# PATTERN-GENERATOR-NODE-SCH.net
KiCad netlist of a schematic drawn in Altium Designer
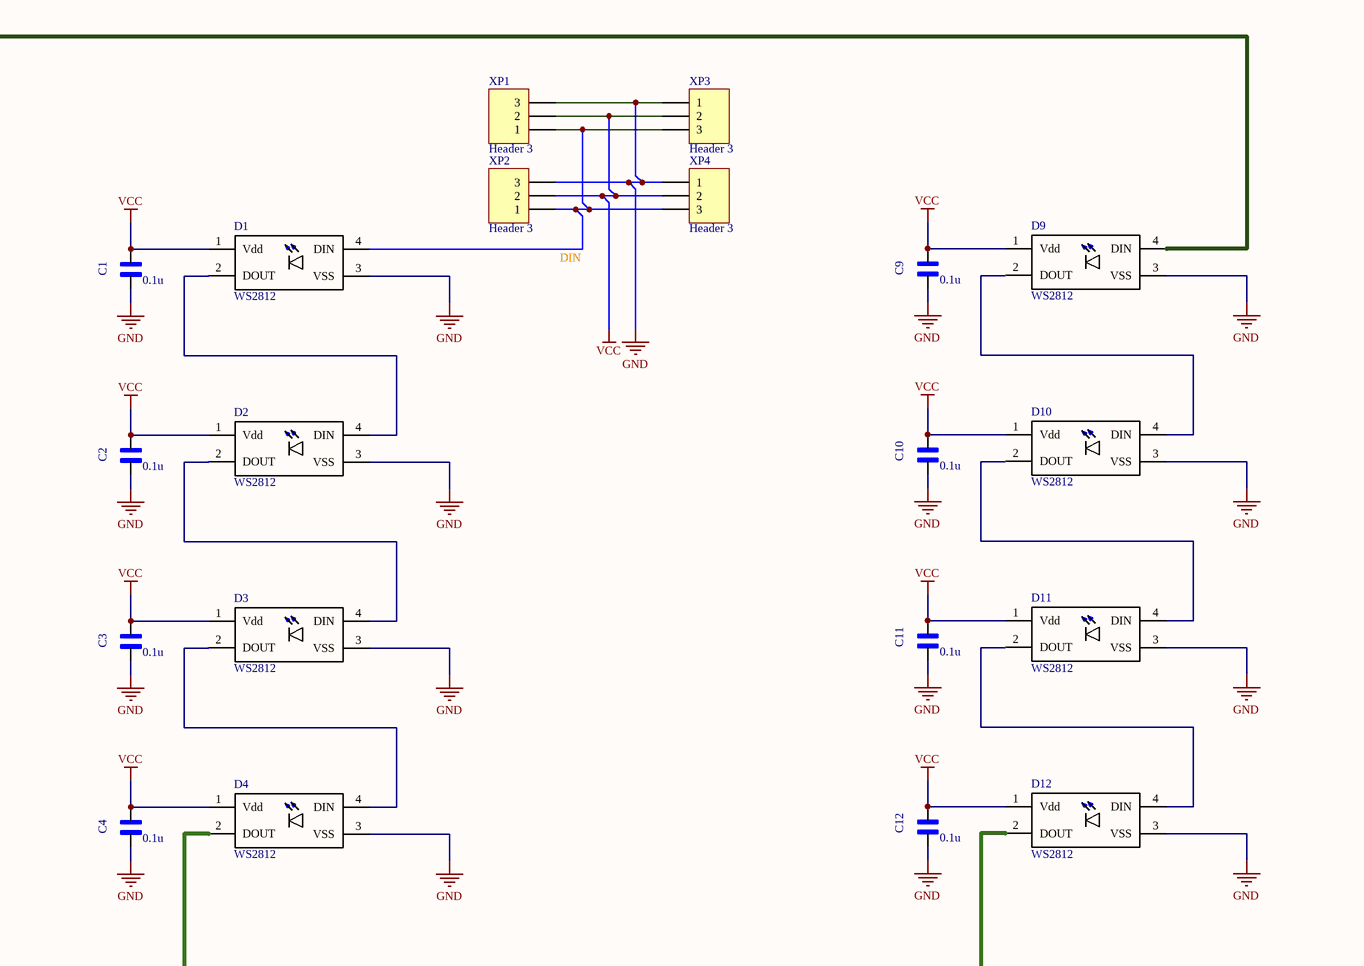
[diagram p0: PATTERN-GENERATOR-NODE-SCH.SchDoc, top left]
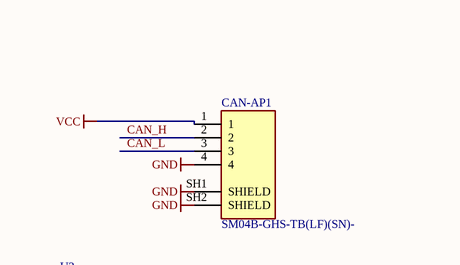
[diagram p1: PATTERN-GENERATOR-NODE-SCH.SchDoc, top right]
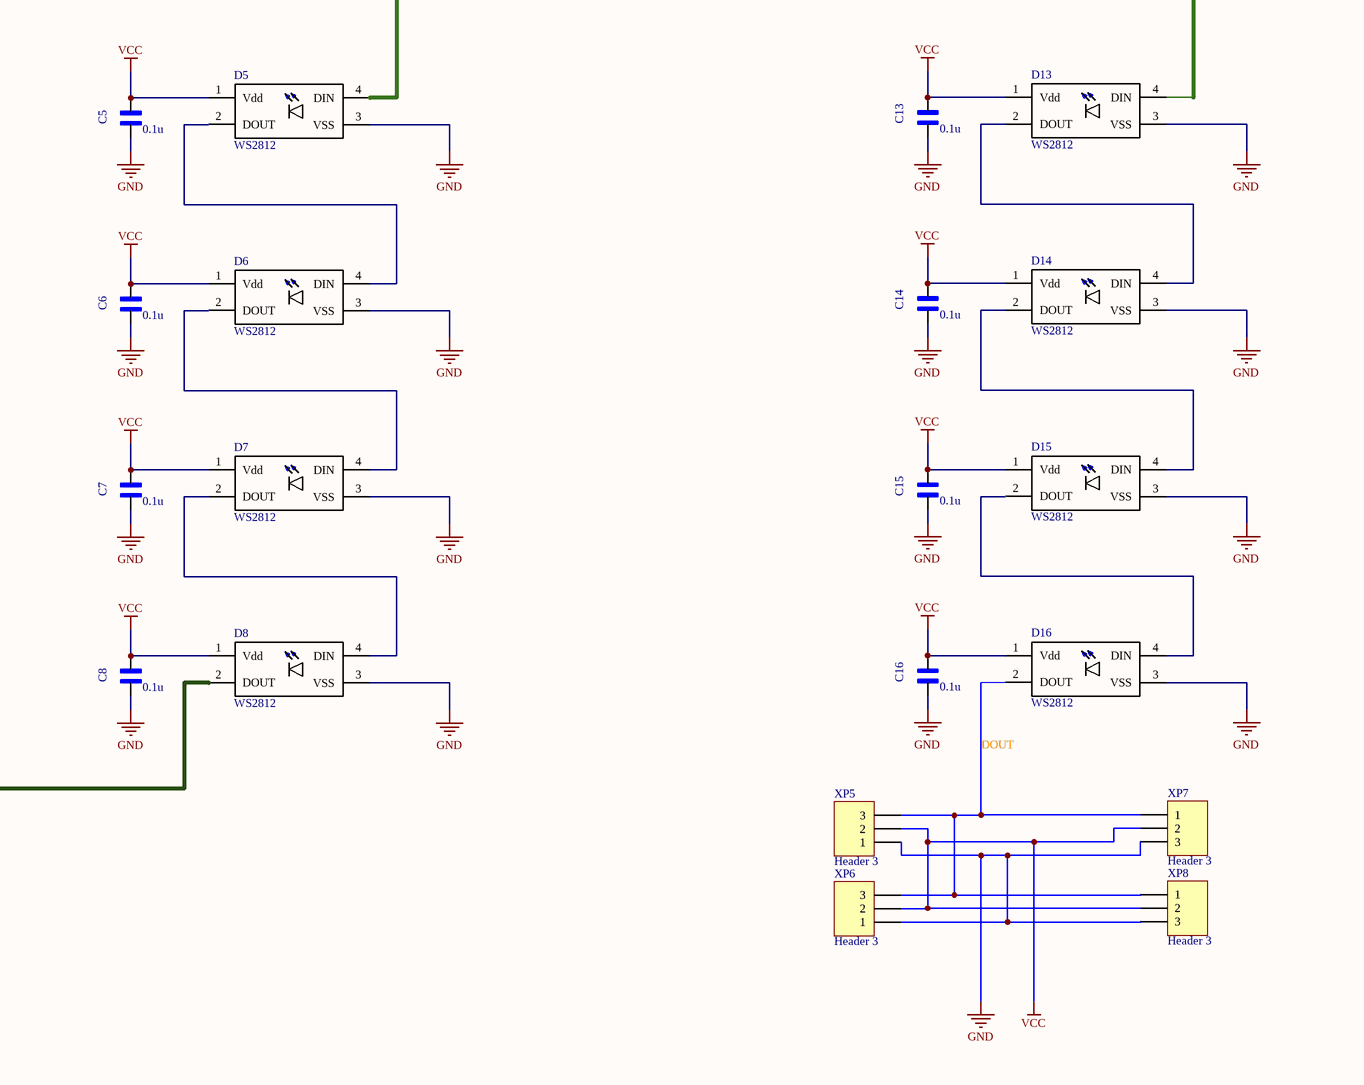
[diagram p2: PATTERN-GENERATOR-NODE-SCH.SchDoc, bottom left]
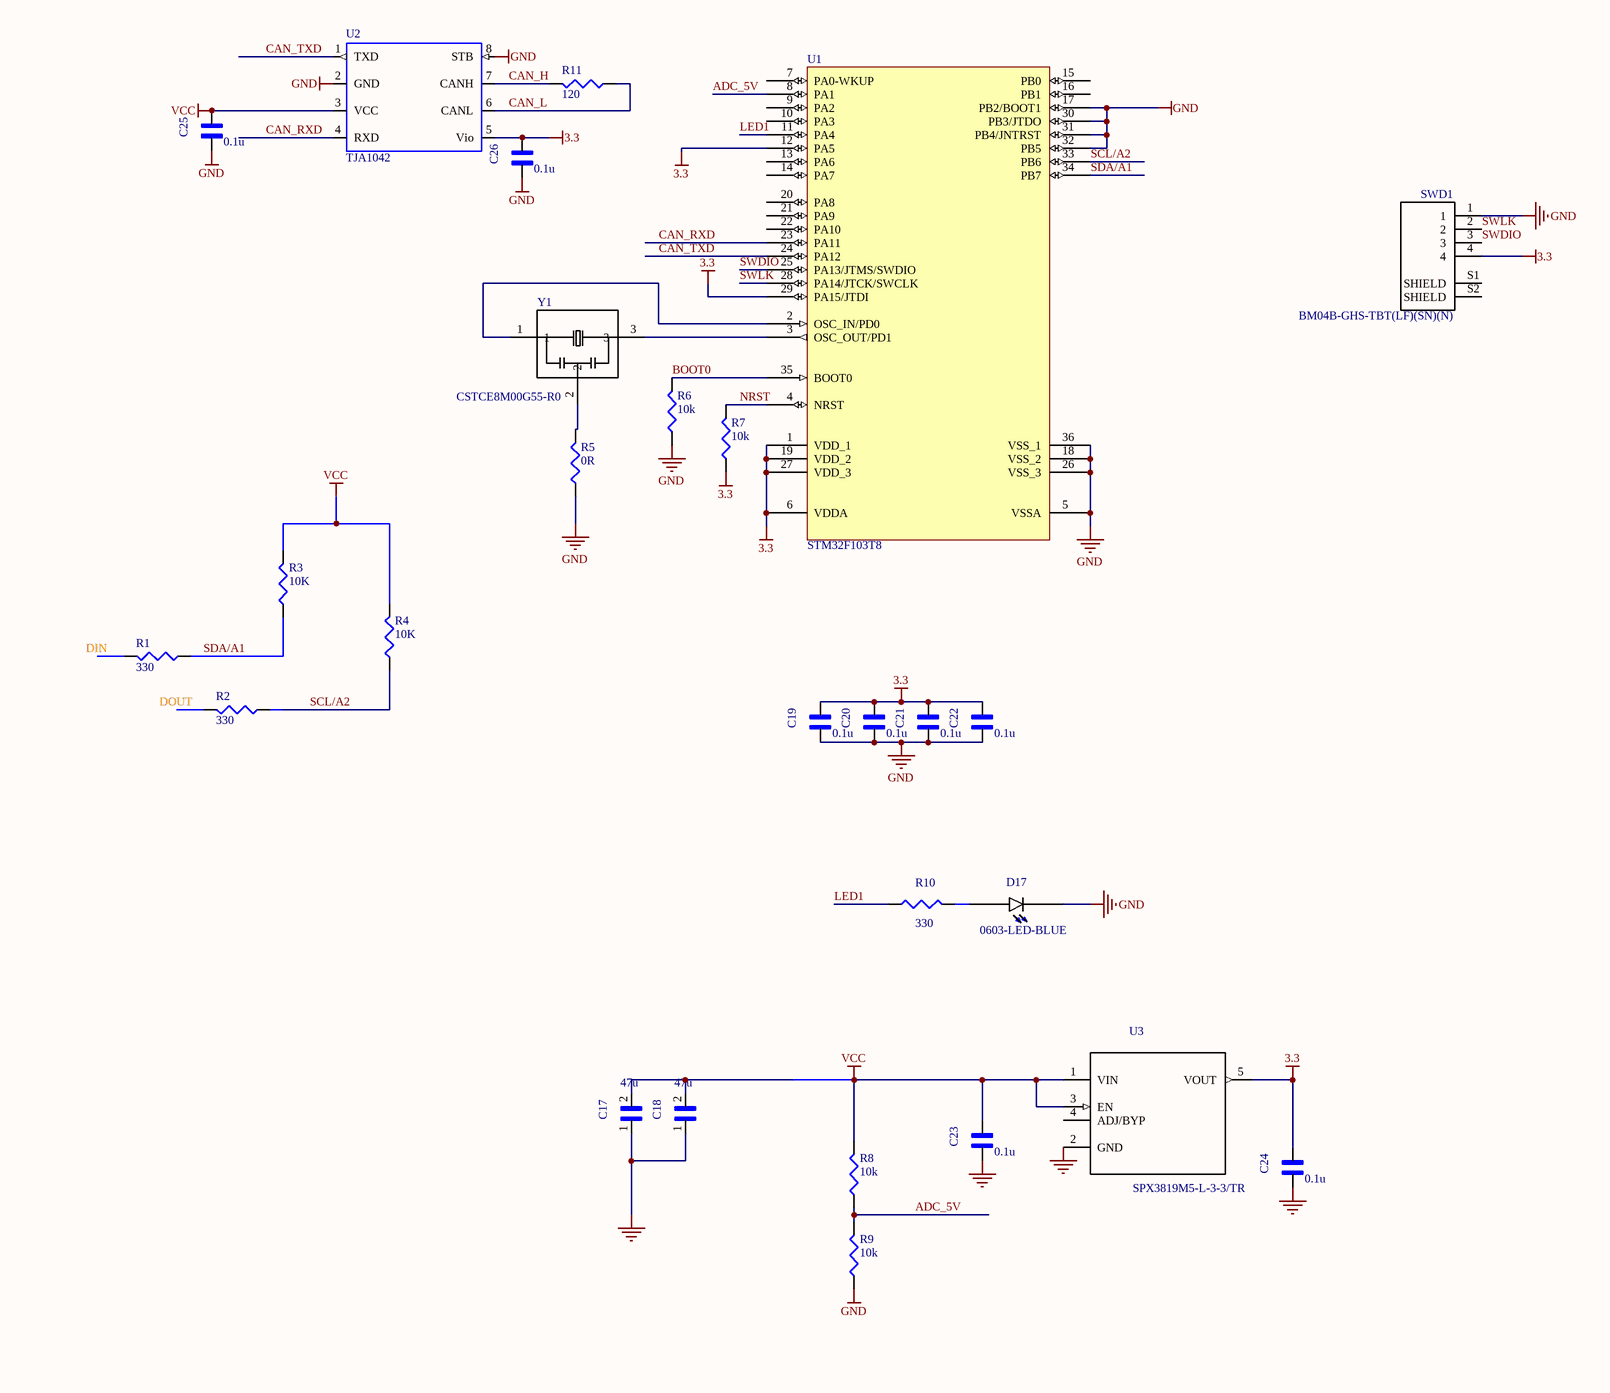
[diagram p3: PATTERN-GENERATOR-NODE-SCH.SchDoc, bottom right]

(export (version "E")
  (design (tool "Eeschema 10.0.6"))
  (components
    (comp (ref "C1")
      (value "0.1u")
      (footprint "*CAPC1608X90")
      (description "Cap Thin Film 0.1uf 50v 0603")
      (fields (field (name "MF") "AVX") (field (name "MP") "GX035C104MAT2-500 or CL10B104JB8NNNC"))
      (libsource (lib "lib") (part "GX035C104MAT2-500"))
    )
    (comp (ref "C2")
      (value "0.1u")
      (footprint "*CAPC1608X90")
      (description "Cap Thin Film 0.1uf 50v 0603")
      (fields (field (name "MF") "AVX") (field (name "MP") "GX035C104MAT2-500 or CL10B104JB8NNNC"))
      (libsource (lib "lib") (part "GX035C104MAT2-500"))
    )
    (comp (ref "C3")
      (value "0.1u")
      (footprint "*CAPC1608X90")
      (description "Cap Thin Film 0.1uf 50v 0603")
      (fields (field (name "MF") "AVX") (field (name "MP") "GX035C104MAT2-500 or CL10B104JB8NNNC"))
      (libsource (lib "lib") (part "GX035C104MAT2-500"))
    )
    (comp (ref "C4")
      (value "0.1u")
      (footprint "*CAPC1608X90")
      (description "Cap Thin Film 0.1uf 50v 0603")
      (fields (field (name "MF") "AVX") (field (name "MP") "GX035C104MAT2-500 or CL10B104JB8NNNC"))
      (libsource (lib "lib") (part "GX035C104MAT2-500"))
    )
    (comp (ref "C5")
      (value "0.1u")
      (footprint "*CAPC1608X90")
      (description "Cap Thin Film 0.1uf 50v 0603")
      (fields (field (name "MF") "AVX") (field (name "MP") "GX035C104MAT2-500 or CL10B104JB8NNNC"))
      (libsource (lib "lib") (part "GX035C104MAT2-500"))
    )
    (comp (ref "C6")
      (value "0.1u")
      (footprint "*CAPC1608X90")
      (description "Cap Thin Film 0.1uf 50v 0603")
      (fields (field (name "MF") "AVX") (field (name "MP") "GX035C104MAT2-500 or CL10B104JB8NNNC"))
      (libsource (lib "lib") (part "GX035C104MAT2-500"))
    )
    (comp (ref "C7")
      (value "0.1u")
      (footprint "*CAPC1608X90")
      (description "Cap Thin Film 0.1uf 50v 0603")
      (fields (field (name "MF") "AVX") (field (name "MP") "GX035C104MAT2-500 or CL10B104JB8NNNC"))
      (libsource (lib "lib") (part "GX035C104MAT2-500"))
    )
    (comp (ref "C8")
      (value "0.1u")
      (footprint "*CAPC1608X90")
      (description "Cap Thin Film 0.1uf 50v 0603")
      (fields (field (name "MF") "AVX") (field (name "MP") "GX035C104MAT2-500 or CL10B104JB8NNNC"))
      (libsource (lib "lib") (part "GX035C104MAT2-500"))
    )
    (comp (ref "C9")
      (value "0.1u")
      (footprint "*CAPC1608X90")
      (description "Cap Thin Film 0.1uf 50v 0603")
      (fields (field (name "MF") "AVX") (field (name "MP") "GX035C104MAT2-500 or CL10B104JB8NNNC"))
      (libsource (lib "lib") (part "GX035C104MAT2-500"))
    )
    (comp (ref "C10")
      (value "0.1u")
      (footprint "*CAPC1608X90")
      (description "Cap Thin Film 0.1uf 50v 0603")
      (fields (field (name "MF") "AVX") (field (name "MP") "GX035C104MAT2-500 or CL10B104JB8NNNC"))
      (libsource (lib "lib") (part "GX035C104MAT2-500"))
    )
    (comp (ref "C11")
      (value "0.1u")
      (footprint "*CAPC1608X90")
      (description "Cap Thin Film 0.1uf 50v 0603")
      (fields (field (name "MF") "AVX") (field (name "MP") "GX035C104MAT2-500 or CL10B104JB8NNNC"))
      (libsource (lib "lib") (part "GX035C104MAT2-500"))
    )
    (comp (ref "C12")
      (value "0.1u")
      (footprint "*CAPC1608X90")
      (description "Cap Thin Film 0.1uf 50v 0603")
      (fields (field (name "MF") "AVX") (field (name "MP") "GX035C104MAT2-500 or CL10B104JB8NNNC"))
      (libsource (lib "lib") (part "GX035C104MAT2-500"))
    )
    (comp (ref "C13")
      (value "0.1u")
      (footprint "*CAPC1608X90")
      (description "Cap Thin Film 0.1uf 50v 0603")
      (fields (field (name "MF") "AVX") (field (name "MP") "GX035C104MAT2-500 or CL10B104JB8NNNC"))
      (libsource (lib "lib") (part "GX035C104MAT2-500"))
    )
    (comp (ref "C14")
      (value "0.1u")
      (footprint "*CAPC1608X90")
      (description "Cap Thin Film 0.1uf 50v 0603")
      (fields (field (name "MF") "AVX") (field (name "MP") "GX035C104MAT2-500 or CL10B104JB8NNNC"))
      (libsource (lib "lib") (part "GX035C104MAT2-500"))
    )
    (comp (ref "C15")
      (value "0.1u")
      (footprint "*CAPC1608X90")
      (description "Cap Thin Film 0.1uf 50v 0603")
      (fields (field (name "MF") "AVX") (field (name "MP") "GX035C104MAT2-500 or CL10B104JB8NNNC"))
      (libsource (lib "lib") (part "GX035C104MAT2-500"))
    )
    (comp (ref "C16")
      (value "0.1u")
      (footprint "*CAPC1608X90")
      (description "Cap Thin Film 0.1uf 50v 0603")
      (fields (field (name "MF") "AVX") (field (name "MP") "GX035C104MAT2-500 or CL10B104JB8NNNC"))
      (libsource (lib "lib") (part "GX035C104MAT2-500"))
    )
    (comp (ref "C17")
      (value "47u")
      (footprint "*CAPC3216X125N")
      (description "Multilayer Ceramic Capacitor, GRM Series, 47 - F, - 10%, X5R, 10 V, 1206 [3216 Metric]")
      (fields (field (name "MF") "Murata Electronics") (field (name "MP") "GRM31CR61A476KE15L"))
      (libsource (lib "lib") (part "GRM31CR61A476KE15L"))
    )
    (comp (ref "C18")
      (value "47u")
      (footprint "*CAPC3216X125N")
      (description "Multilayer Ceramic Capacitor, GRM Series, 47 - F, - 10%, X5R, 10 V, 1206 [3216 Metric]")
      (fields (field (name "MF") "Murata Electronics") (field (name "MP") "GRM31CR61A476KE15L"))
      (libsource (lib "lib") (part "GRM31CR61A476KE15L"))
    )
    (comp (ref "C19")
      (value "0.1u")
      (footprint "*CAPC1608X90")
      (description "Cap Thin Film 0.1uf 50v 0603")
      (fields (field (name "MF") "AVX") (field (name "MP") "GX035C104MAT2-500 or CL10B104JB8NNNC"))
      (libsource (lib "lib") (part "GX035C104MAT2-500"))
    )
    (comp (ref "C20")
      (value "0.1u")
      (footprint "*CAPC1608X90")
      (description "Cap Thin Film 0.1uf 50v 0603")
      (fields (field (name "MF") "AVX") (field (name "MP") "GX035C104MAT2-500 or CL10B104JB8NNNC"))
      (libsource (lib "lib") (part "GX035C104MAT2-500"))
    )
    (comp (ref "C21")
      (value "0.1u")
      (footprint "*CAPC1608X90")
      (description "Cap Thin Film 0.1uf 50v 0603")
      (fields (field (name "MF") "AVX") (field (name "MP") "GX035C104MAT2-500 or CL10B104JB8NNNC"))
      (libsource (lib "lib") (part "GX035C104MAT2-500"))
    )
    (comp (ref "C22")
      (value "0.1u")
      (footprint "*CAPC1608X90")
      (description "Cap Thin Film 0.1uf 50v 0603")
      (fields (field (name "MF") "AVX") (field (name "MP") "GX035C104MAT2-500 or CL10B104JB8NNNC"))
      (libsource (lib "lib") (part "GX035C104MAT2-500"))
    )
    (comp (ref "C23")
      (value "0.1u")
      (footprint "*CAPC1608X90")
      (description "Cap Thin Film 0.1uf 50v 0603")
      (fields (field (name "MF") "AVX") (field (name "MP") "GX035C104MAT2-500"))
      (libsource (lib "lib") (part "GX035C104MAT2-500"))
    )
    (comp (ref "C24")
      (value "0.1u")
      (footprint "*CAPC1608X90")
      (description "Cap Thin Film 0.1uf 50v 0603")
      (fields (field (name "MF") "AVX") (field (name "MP") "GX035C104MAT2-500"))
      (libsource (lib "lib") (part "GX035C104MAT2-500"))
    )
    (comp (ref "C25")
      (value "0.1u")
      (footprint "*CAPC1608X90")
      (description "Cap Thin Film 0.1uf 50v 0603")
      (fields (field (name "MF") "AVX") (field (name "MP") "GX035C104MAT2-500 or CL10B104JB8NNNC"))
      (libsource (lib "lib") (part "GX035C104MAT2-500"))
    )
    (comp (ref "C26")
      (value "0.1u")
      (footprint "*CAPC1608X90")
      (description "Cap Thin Film 0.1uf 50v 0603")
      (fields (field (name "MF") "AVX") (field (name "MP") "GX035C104MAT2-500 or CL10B104JB8NNNC"))
      (libsource (lib "lib") (part "GX035C104MAT2-500"))
    )
    (comp (ref "CAN-AP1")
      (value "SM04B-GHS-TB(LF)(SN)-")
      (footprint "JST_SM04B-GHS-TB(LF)(SN)-")
      (description "Connector Header Surface Mount, Right Angle 4 position 0.049 _1.25mm_")
      (fields (field (name "MP") "SM04B-GHS-TB(LF)(SN)") (field (name "MF") "JST Sales"))
      (libsource (lib "lib") (part "SM04B-GHS-TB(LF)(SN)-"))
    )
    (comp (ref "D1")
      (value "WS2812")
      (footprint "LED_WS2812")
      (description "Addressable Lighting - 5 LED Discrete Serial _Shift Register_ Red, Green, Blue _RGB_ 5.00mm Dia")
      (fields (field (name "MF") "SparkFun Electronics"))
      (libsource (lib "lib") (part "WS2812"))
    )
    (comp (ref "D2")
      (value "WS2812")
      (footprint "LED_WS2812")
      (description "Addressable Lighting - 5 LED Discrete Serial _Shift Register_ Red, Green, Blue _RGB_ 5.00mm Dia")
      (fields (field (name "MF") "SparkFun Electronics"))
      (libsource (lib "lib") (part "WS2812"))
    )
    (comp (ref "D3")
      (value "WS2812")
      (footprint "LED_WS2812")
      (description "Addressable Lighting - 5 LED Discrete Serial _Shift Register_ Red, Green, Blue _RGB_ 5.00mm Dia")
      (fields (field (name "MF") "SparkFun Electronics"))
      (libsource (lib "lib") (part "WS2812"))
    )
    (comp (ref "D4")
      (value "WS2812")
      (footprint "LED_WS2812")
      (description "Addressable Lighting - 5 LED Discrete Serial _Shift Register_ Red, Green, Blue _RGB_ 5.00mm Dia")
      (fields (field (name "MF") "SparkFun Electronics"))
      (libsource (lib "lib") (part "WS2812"))
    )
    (comp (ref "D5")
      (value "WS2812")
      (footprint "LED_WS2812")
      (description "Addressable Lighting - 5 LED Discrete Serial _Shift Register_ Red, Green, Blue _RGB_ 5.00mm Dia")
      (fields (field (name "MF") "SparkFun Electronics"))
      (libsource (lib "lib") (part "WS2812"))
    )
    (comp (ref "D6")
      (value "WS2812")
      (footprint "LED_WS2812")
      (description "Addressable Lighting - 5 LED Discrete Serial _Shift Register_ Red, Green, Blue _RGB_ 5.00mm Dia")
      (fields (field (name "MF") "SparkFun Electronics"))
      (libsource (lib "lib") (part "WS2812"))
    )
    (comp (ref "D7")
      (value "WS2812")
      (footprint "LED_WS2812")
      (description "Addressable Lighting - 5 LED Discrete Serial _Shift Register_ Red, Green, Blue _RGB_ 5.00mm Dia")
      (fields (field (name "MF") "SparkFun Electronics"))
      (libsource (lib "lib") (part "WS2812"))
    )
    (comp (ref "D8")
      (value "WS2812")
      (footprint "LED_WS2812")
      (description "Addressable Lighting - 5 LED Discrete Serial _Shift Register_ Red, Green, Blue _RGB_ 5.00mm Dia")
      (fields (field (name "MF") "SparkFun Electronics"))
      (libsource (lib "lib") (part "WS2812"))
    )
    (comp (ref "D9")
      (value "WS2812")
      (footprint "LED_WS2812")
      (description "Addressable Lighting - 5 LED Discrete Serial _Shift Register_ Red, Green, Blue _RGB_ 5.00mm Dia")
      (fields (field (name "MF") "SparkFun Electronics"))
      (libsource (lib "lib") (part "WS2812"))
    )
    (comp (ref "D10")
      (value "WS2812")
      (footprint "LED_WS2812")
      (description "Addressable Lighting - 5 LED Discrete Serial _Shift Register_ Red, Green, Blue _RGB_ 5.00mm Dia")
      (fields (field (name "MF") "SparkFun Electronics"))
      (libsource (lib "lib") (part "WS2812"))
    )
    (comp (ref "D11")
      (value "WS2812")
      (footprint "LED_WS2812")
      (description "Addressable Lighting - 5 LED Discrete Serial _Shift Register_ Red, Green, Blue _RGB_ 5.00mm Dia")
      (fields (field (name "MF") "SparkFun Electronics"))
      (libsource (lib "lib") (part "WS2812"))
    )
    (comp (ref "D12")
      (value "WS2812")
      (footprint "LED_WS2812")
      (description "Addressable Lighting - 5 LED Discrete Serial _Shift Register_ Red, Green, Blue _RGB_ 5.00mm Dia")
      (fields (field (name "MF") "SparkFun Electronics"))
      (libsource (lib "lib") (part "WS2812"))
    )
    (comp (ref "D13")
      (value "WS2812")
      (footprint "LED_WS2812")
      (description "Addressable Lighting - 5 LED Discrete Serial _Shift Register_ Red, Green, Blue _RGB_ 5.00mm Dia")
      (fields (field (name "MF") "SparkFun Electronics"))
      (libsource (lib "lib") (part "WS2812"))
    )
    (comp (ref "D14")
      (value "WS2812")
      (footprint "LED_WS2812")
      (description "Addressable Lighting - 5 LED Discrete Serial _Shift Register_ Red, Green, Blue _RGB_ 5.00mm Dia")
      (fields (field (name "MF") "SparkFun Electronics"))
      (libsource (lib "lib") (part "WS2812"))
    )
    (comp (ref "D15")
      (value "WS2812")
      (footprint "LED_WS2812")
      (description "Addressable Lighting - 5 LED Discrete Serial _Shift Register_ Red, Green, Blue _RGB_ 5.00mm Dia")
      (fields (field (name "MF") "SparkFun Electronics"))
      (libsource (lib "lib") (part "WS2812"))
    )
    (comp (ref "D16")
      (value "WS2812")
      (footprint "LED_WS2812")
      (description "Addressable Lighting - 5 LED Discrete Serial _Shift Register_ Red, Green, Blue _RGB_ 5.00mm Dia")
      (fields (field (name "MF") "SparkFun Electronics"))
      (libsource (lib "lib") (part "WS2812"))
    )
    (comp (ref "D17")
      (value "0603-LED-BLUE")
      (footprint "*LEDM1608X80_LTE-C1906R-14(Primary)")
      (description "LED IrLED Chip LED 2-Pin SMD T/R")
      (libsource (lib "lib") (part "LTE-C1906R-14"))
    )
    (comp (ref "R1")
      (value "330")
      (footprint "J1-0603")
      (description "Resistor")
      (fields (field (name "MP") "4.7K 1% 0603") (field (name "Comment") "Res3"))
      (libsource (lib "Miscellaneous Devices") (part "Res3"))
    )
    (comp (ref "R2")
      (value "330")
      (footprint "J1-0603")
      (description "Resistor")
      (fields (field (name "MP") "4.7K 1% 0603") (field (name "Comment") "Res3"))
      (libsource (lib "Miscellaneous Devices") (part "Res3"))
    )
    (comp (ref "R3")
      (value "10K")
      (footprint "J1-0603")
      (description "Resistor")
      (fields (field (name "MP") "4.7K 1% 0603") (field (name "Comment") "Res3"))
      (libsource (lib "Miscellaneous Devices") (part "Res3"))
    )
    (comp (ref "R4")
      (value "10K")
      (footprint "J1-0603")
      (description "Resistor")
      (fields (field (name "MP") "4.7K 1% 0603") (field (name "Comment") "Res3"))
      (libsource (lib "Miscellaneous Devices") (part "Res3"))
    )
    (comp (ref "R5")
      (value "0R")
      (footprint "J1-0603")
      (description "10 kOhms 1 0.1 W 1 10 W Chip Resistor 0603 1608 Metric Thick Film")
      (fields (field (name "MF") "Yageo or NXP") (field (name "MP") "10K 1% 0603"))
      (libsource (lib "CAN_NODE_MINI") (part "RC0603FR-0710KL"))
    )
    (comp (ref "R6")
      (value "10k")
      (footprint "J1-0603")
      (description "10 kOhms 1 0.1 W 1 10 W Chip Resistor 0603 1608 Metric Thick Film")
      (fields (field (name "MF") "Yageo or NXP") (field (name "MP") "10K 1% 0603"))
      (libsource (lib "CAN_NODE_MINI") (part "RC0603FR-0710KL"))
    )
    (comp (ref "R7")
      (value "10k")
      (footprint "J1-0603")
      (description "10 kOhms 1 0.1 W 1 10 W Chip Resistor 0603 1608 Metric Thick Film")
      (fields (field (name "MF") "Yageo or NXP") (field (name "MP") "10K 1% 0603"))
      (libsource (lib "CAN_NODE_MINI") (part "RC0603FR-0710KL"))
    )
    (comp (ref "R8")
      (value "10k")
      (footprint "J1-0603")
      (description "10 kOhms 1 0.1 W 1 10 W Chip Resistor 0603 1608 Metric Thick Film")
      (fields (field (name "MF") "Yageo or NXP") (field (name "MP") "10K 1% 0603"))
      (libsource (lib "CAN_NODE_MINI") (part "RC0603FR-0710KL"))
    )
    (comp (ref "R9")
      (value "10k")
      (footprint "J1-0603")
      (description "10 kOhms 1 0.1 W 1 10 W Chip Resistor 0603 1608 Metric Thick Film")
      (fields (field (name "MF") "Yageo or NXP") (field (name "MP") "10K 1% 0603"))
      (libsource (lib "CAN_NODE_MINI") (part "RC0603FR-0710KL"))
    )
    (comp (ref "R10")
      (value "330")
      (footprint "J1-0603")
      (description "Resistor")
      (fields (field (name "MP") "RC0603FR-07330RL") (field (name "Comment") "Res3"))
      (libsource (lib "Miscellaneous Devices") (part "Res3"))
    )
    (comp (ref "R11")
      (value "120")
      (footprint "J1-0603")
      (description "120 Ohms 1 0.1 W 1 10 W Chip Resistor 0603 1608 Metric Thick Film")
      (fields (field (name "MP") "RC0603FR-07120RL") (field (name "Comment") "Res3"))
      (libsource (lib "Miscellaneous Devices") (part "Res3"))
    )
    (comp (ref "SWD1")
      (value "BM04B-GHS-TBT(LF)(SN)(N)")
      (footprint "JST_BM04B-GHS-holes")
      (description "Conn Shrouded Header HDR 4 POS 1.25mm Solder ST SMD Reel")
      (fields (field (name "MF") "JST Sales") (field (name "MP") "SM04B-GHS-TB(LF)(SN)"))
      (libsource (lib "lib") (part "BM04B-GHS-TBT(LF)(SN)(N)"))
    )
    (comp (ref "U1")
      (value "STM32F103T8")
      (footprint "*QFN50P600X600X100-37N")
      (description "STM32F103T8U6, Микроконтроллер 32BIT ARM 64K FLASH [VFQFPN-36]")
      (fields (field (name "MF") "STM") (field (name "MP") "STM32F103T8U6"))
      (libsource (lib "lib") (part "STM32F103T8"))
    )
    (comp (ref "U2")
      (value "TJA1042")
      (footprint "SOT782-1")
      (description "1/1 Transceiver Half CANbus 8-SO")
      (fields (field (name "MF") "NXP USA"))
      (libsource (lib "lib") (part "TJA1042"))
    )
    (comp (ref "U3")
      (value "SPX3819M5-L-3-3/TR")
      (footprint "*SOT95P280X145-5N")
      (description "Low Dropout Voltage Regulator, Adjustable 0.5A, В±1%, 2.5 to 16 Vin, 5-Pin SOT-23")
      (fields (field (name "MF") "MaxLinear, Inc."))
      (libsource (lib "DC_DC") (part "SPX3819M5-L"))
    )
    (comp (ref "XP1")
      (value "Header 3")
      (footprint "HDR Side 3 pin")
      (description "Header, 3-Pin")
      (fields (field (name "PUBLISHER") "Altium Limited"))
      (libsource (lib "lib") (part "Header 3"))
    )
    (comp (ref "XP2")
      (value "Header 3")
      (footprint "HDR Side 3 pin")
      (description "Header, 3-Pin")
      (fields (field (name "PUBLISHER") "Altium Limited"))
      (libsource (lib "lib") (part "Header 3"))
    )
    (comp (ref "XP3")
      (value "Header 3")
      (footprint "HDR Side 3 pin")
      (description "Header, 3-Pin")
      (fields (field (name "PUBLISHER") "Altium Limited"))
      (libsource (lib "") (part "Header 3_1"))
    )
    (comp (ref "XP4")
      (value "Header 3")
      (footprint "HDR Side 3 pin")
      (description "Header, 3-Pin")
      (fields (field (name "PUBLISHER") "Altium Limited"))
      (libsource (lib "") (part "Header 3_1"))
    )
    (comp (ref "XP5")
      (value "Header 3")
      (footprint "HDR Side 3 pin")
      (description "Header, 3-Pin")
      (fields (field (name "PUBLISHER") "Altium Limited"))
      (libsource (lib "lib") (part "Header 3"))
    )
    (comp (ref "XP6")
      (value "Header 3")
      (footprint "HDR Side 3 pin")
      (description "Header, 3-Pin")
      (fields (field (name "PUBLISHER") "Altium Limited"))
      (libsource (lib "lib") (part "Header 3"))
    )
    (comp (ref "XP7")
      (value "Header 3")
      (footprint "HDR Side 3 pin")
      (description "Header, 3-Pin")
      (fields (field (name "PUBLISHER") "Altium Limited"))
      (libsource (lib "") (part "Header 3_1"))
    )
    (comp (ref "XP8")
      (value "Header 3")
      (footprint "HDR Side 3 pin")
      (description "Header, 3-Pin")
      (fields (field (name "PUBLISHER") "Altium Limited"))
      (libsource (lib "") (part "Header 3_1"))
    )
    (comp (ref "Y1")
      (value "CSTCE8M00G55-R0")
      (footprint "*OSC_CSTCE8M00G55-R0")
      (description "Ceramic Resonator 8MHz ??0.5% _Tol_ ??0.2% _Stability_ 33pF 40Ohm 3-Pin CSMD T/R")
      (fields (field (name "MF") "Murata"))
      (libsource (lib "DC_DC") (part "CSTCE8M00G55-R0"))
    )
  )
  (nets
    (net (code "1") (name "/ADC_5V") (class "Default")
      (node (ref "R8") (pin "1") (pinfunction "1_1") (pintype "passive"))
      (node (ref "R9") (pin "2") (pinfunction "2_2") (pintype "passive"))
      (node (ref "U1") (pin "8") (pinfunction "PA1_8") (pintype "bidirectional"))
    )
    (net (code "2") (name "/BOOT0") (class "Default")
      (node (ref "R6") (pin "2") (pinfunction "2_2") (pintype "passive"))
      (node (ref "U1") (pin "35") (pinfunction "BOOT0_35") (pintype "input"))
    )
    (net (code "3") (name "/CAN_H") (class "Default")
      (node (ref "CAN-AP1") (pin "2") (pinfunction "2_2") (pintype "passive"))
      (node (ref "R11") (pin "2") (pinfunction "2_2") (pintype "passive"))
      (node (ref "U2") (pin "7") (pinfunction "CANH_7") (pintype "bidirectional"))
    )
    (net (code "4") (name "/CAN_L") (class "Default")
      (node (ref "CAN-AP1") (pin "3") (pinfunction "3_3") (pintype "passive"))
      (node (ref "R11") (pin "1") (pinfunction "1_1") (pintype "passive"))
      (node (ref "U2") (pin "6") (pinfunction "CANL_6") (pintype "bidirectional"))
    )
    (net (code "5") (name "/CAN_RXD") (class "Default")
      (node (ref "U1") (pin "23") (pinfunction "PA11_23") (pintype "bidirectional"))
      (node (ref "U2") (pin "4") (pinfunction "RXD_4") (pintype "bidirectional"))
    )
    (net (code "6") (name "/CAN_TXD") (class "Default")
      (node (ref "U1") (pin "24") (pinfunction "PA12_24") (pintype "bidirectional"))
      (node (ref "U2") (pin "1") (pinfunction "TXD_1") (pintype "output"))
    )
    (net (code "7") (name "/DIN") (class "Default")
      (node (ref "D1") (pin "4") (pinfunction "DIN_4") (pintype "power_in"))
      (node (ref "R1") (pin "2") (pinfunction "2_2") (pintype "passive"))
      (node (ref "XP1") (pin "1") (pinfunction "1_1") (pintype "passive"))
      (node (ref "XP2") (pin "1") (pinfunction "1_1") (pintype "passive"))
      (node (ref "XP3") (pin "3") (pinfunction "3_3") (pintype "passive"))
      (node (ref "XP4") (pin "3") (pinfunction "3_3") (pintype "passive"))
    )
    (net (code "8") (name "/DOUT") (class "Default")
      (node (ref "D16") (pin "2") (pinfunction "DOUT_2") (pintype "power_in"))
      (node (ref "R2") (pin "2") (pinfunction "2_2") (pintype "passive"))
      (node (ref "XP5") (pin "3") (pinfunction "3_3") (pintype "passive"))
      (node (ref "XP6") (pin "3") (pinfunction "3_3") (pintype "passive"))
      (node (ref "XP7") (pin "1") (pinfunction "1_1") (pintype "passive"))
      (node (ref "XP8") (pin "1") (pinfunction "1_1") (pintype "passive"))
    )
    (net (code "9") (name "/LED1") (class "Default")
      (node (ref "R10") (pin "1") (pinfunction "1_1") (pintype "passive"))
      (node (ref "U1") (pin "11") (pinfunction "PA4_11") (pintype "bidirectional"))
    )
    (net (code "10") (name "/NRST") (class "Default")
      (node (ref "R7") (pin "2") (pinfunction "2_2") (pintype "passive"))
      (node (ref "U1") (pin "4") (pinfunction "NRST_4") (pintype "bidirectional"))
    )
    (net (code "11") (name "/SCL{slash}A2") (class "Default")
      (node (ref "R2") (pin "1") (pinfunction "1_1") (pintype "passive"))
      (node (ref "R4") (pin "1") (pinfunction "1_1") (pintype "passive"))
      (node (ref "U1") (pin "33") (pinfunction "PB6_33") (pintype "bidirectional"))
    )
    (net (code "12") (name "/SDA{slash}A1") (class "Default")
      (node (ref "R1") (pin "1") (pinfunction "1_1") (pintype "passive"))
      (node (ref "R3") (pin "1") (pinfunction "1_1") (pintype "passive"))
      (node (ref "U1") (pin "34") (pinfunction "PB7_34") (pintype "bidirectional"))
    )
    (net (code "13") (name "/SWDIO") (class "Default")
      (node (ref "SWD1") (pin "3") (pinfunction "3_3") (pintype "passive"))
      (node (ref "U1") (pin "25") (pinfunction "PA13/JTMS/SWDIO_25") (pintype "bidirectional"))
    )
    (net (code "14") (name "/SWLK") (class "Default")
      (node (ref "SWD1") (pin "2") (pinfunction "2_2") (pintype "passive"))
      (node (ref "U1") (pin "28") (pinfunction "PA14/JTCK/SWCLK_28") (pintype "bidirectional"))
    )
    (net (code "15") (name "3.3") (class "Default")
      (node (ref "C19") (pin "1") (pinfunction "1_1") (pintype "passive"))
      (node (ref "C20") (pin "1") (pinfunction "1_1") (pintype "passive"))
      (node (ref "C21") (pin "1") (pinfunction "1_1") (pintype "passive"))
      (node (ref "C22") (pin "1") (pinfunction "1_1") (pintype "passive"))
      (node (ref "C24") (pin "1") (pinfunction "1_1") (pintype "passive"))
      (node (ref "C26") (pin "1") (pinfunction "1_1") (pintype "passive"))
      (node (ref "R7") (pin "1") (pinfunction "1_1") (pintype "passive"))
      (node (ref "SWD1") (pin "4") (pinfunction "4_4") (pintype "passive"))
      (node (ref "U1") (pin "1") (pinfunction "VDD_1_1") (pintype "power_in"))
      (node (ref "U1") (pin "12") (pinfunction "PA5_12") (pintype "bidirectional"))
      (node (ref "U1") (pin "19") (pinfunction "VDD_2_19") (pintype "power_in"))
      (node (ref "U1") (pin "27") (pinfunction "VDD_3_27") (pintype "power_in"))
      (node (ref "U1") (pin "29") (pinfunction "PA15/JTDI_29") (pintype "bidirectional"))
      (node (ref "U1") (pin "6") (pinfunction "VDDA_6") (pintype "power_in"))
      (node (ref "U2") (pin "5") (pinfunction "Vio_5") (pintype "power_in"))
      (node (ref "U3") (pin "5") (pinfunction "VOUT_5") (pintype "output"))
    )
    (net (code "16") (name "GND") (class "Default")
      (node (ref "C1") (pin "2") (pinfunction "2_2") (pintype "passive"))
      (node (ref "C10") (pin "2") (pinfunction "2_2") (pintype "passive"))
      (node (ref "C11") (pin "2") (pinfunction "2_2") (pintype "passive"))
      (node (ref "C12") (pin "2") (pinfunction "2_2") (pintype "passive"))
      (node (ref "C13") (pin "2") (pinfunction "2_2") (pintype "passive"))
      (node (ref "C14") (pin "2") (pinfunction "2_2") (pintype "passive"))
      (node (ref "C15") (pin "2") (pinfunction "2_2") (pintype "passive"))
      (node (ref "C16") (pin "2") (pinfunction "2_2") (pintype "passive"))
      (node (ref "C17") (pin "1") (pinfunction "1_1") (pintype "passive"))
      (node (ref "C18") (pin "1") (pinfunction "1_1") (pintype "passive"))
      (node (ref "C19") (pin "2") (pinfunction "2_2") (pintype "passive"))
      (node (ref "C2") (pin "2") (pinfunction "2_2") (pintype "passive"))
      (node (ref "C20") (pin "2") (pinfunction "2_2") (pintype "passive"))
      (node (ref "C21") (pin "2") (pinfunction "2_2") (pintype "passive"))
      (node (ref "C22") (pin "2") (pinfunction "2_2") (pintype "passive"))
      (node (ref "C23") (pin "2") (pinfunction "2_2") (pintype "passive"))
      (node (ref "C24") (pin "2") (pinfunction "2_2") (pintype "passive"))
      (node (ref "C25") (pin "2") (pinfunction "2_2") (pintype "passive"))
      (node (ref "C26") (pin "2") (pinfunction "2_2") (pintype "passive"))
      (node (ref "C3") (pin "2") (pinfunction "2_2") (pintype "passive"))
      (node (ref "C4") (pin "2") (pinfunction "2_2") (pintype "passive"))
      (node (ref "C5") (pin "2") (pinfunction "2_2") (pintype "passive"))
      (node (ref "C6") (pin "2") (pinfunction "2_2") (pintype "passive"))
      (node (ref "C7") (pin "2") (pinfunction "2_2") (pintype "passive"))
      (node (ref "C8") (pin "2") (pinfunction "2_2") (pintype "passive"))
      (node (ref "C9") (pin "2") (pinfunction "2_2") (pintype "passive"))
      (node (ref "CAN-AP1") (pin "4") (pinfunction "4_4") (pintype "passive"))
      (node (ref "CAN-AP1") (pin "SH1") (pinfunction "SHIELD_SH1") (pintype "power_in"))
      (node (ref "CAN-AP1") (pin "SH2") (pinfunction "SHIELD_SH2") (pintype "power_in"))
      (node (ref "D1") (pin "3") (pinfunction "VSS_3") (pintype "power_in"))
      (node (ref "D10") (pin "3") (pinfunction "VSS_3") (pintype "power_in"))
      (node (ref "D11") (pin "3") (pinfunction "VSS_3") (pintype "power_in"))
      (node (ref "D12") (pin "3") (pinfunction "VSS_3") (pintype "power_in"))
      (node (ref "D13") (pin "3") (pinfunction "VSS_3") (pintype "power_in"))
      (node (ref "D14") (pin "3") (pinfunction "VSS_3") (pintype "power_in"))
      (node (ref "D15") (pin "3") (pinfunction "VSS_3") (pintype "power_in"))
      (node (ref "D16") (pin "3") (pinfunction "VSS_3") (pintype "power_in"))
      (node (ref "D17") (pin "C") (pinfunction "C_C") (pintype "passive"))
      (node (ref "D2") (pin "3") (pinfunction "VSS_3") (pintype "power_in"))
      (node (ref "D3") (pin "3") (pinfunction "VSS_3") (pintype "power_in"))
      (node (ref "D4") (pin "3") (pinfunction "VSS_3") (pintype "power_in"))
      (node (ref "D5") (pin "3") (pinfunction "VSS_3") (pintype "power_in"))
      (node (ref "D6") (pin "3") (pinfunction "VSS_3") (pintype "power_in"))
      (node (ref "D7") (pin "3") (pinfunction "VSS_3") (pintype "power_in"))
      (node (ref "D8") (pin "3") (pinfunction "VSS_3") (pintype "power_in"))
      (node (ref "D9") (pin "3") (pinfunction "VSS_3") (pintype "power_in"))
      (node (ref "R5") (pin "1") (pinfunction "1_1") (pintype "passive"))
      (node (ref "R6") (pin "1") (pinfunction "1_1") (pintype "passive"))
      (node (ref "R9") (pin "1") (pinfunction "1_1") (pintype "passive"))
      (node (ref "SWD1") (pin "1") (pinfunction "1_1") (pintype "passive"))
      (node (ref "U1") (pin "17") (pinfunction "PB2/BOOT1_17") (pintype "bidirectional"))
      (node (ref "U1") (pin "18") (pinfunction "VSS_2_18") (pintype "power_in"))
      (node (ref "U1") (pin "26") (pinfunction "VSS_3_26") (pintype "power_in"))
      (node (ref "U1") (pin "30") (pinfunction "PB3/JTDO_30") (pintype "bidirectional"))
      (node (ref "U1") (pin "31") (pinfunction "PB4/JNTRST_31") (pintype "bidirectional"))
      (node (ref "U1") (pin "32") (pinfunction "PB5_32") (pintype "bidirectional"))
      (node (ref "U1") (pin "36") (pinfunction "VSS_1_36") (pintype "power_in"))
      (node (ref "U1") (pin "5") (pinfunction "VSSA_5") (pintype "power_in"))
      (node (ref "U2") (pin "2") (pinfunction "GND_2") (pintype "power_in"))
      (node (ref "U2") (pin "8") (pinfunction "STB_8") (pintype "input"))
      (node (ref "U3") (pin "2") (pinfunction "GND_2") (pintype "passive"))
      (node (ref "XP1") (pin "3") (pinfunction "3_3") (pintype "passive"))
      (node (ref "XP2") (pin "3") (pinfunction "3_3") (pintype "passive"))
      (node (ref "XP3") (pin "1") (pinfunction "1_1") (pintype "passive"))
      (node (ref "XP4") (pin "1") (pinfunction "1_1") (pintype "passive"))
      (node (ref "XP5") (pin "1") (pinfunction "1_1") (pintype "passive"))
      (node (ref "XP6") (pin "1") (pinfunction "1_1") (pintype "passive"))
      (node (ref "XP7") (pin "3") (pinfunction "3_3") (pintype "passive"))
      (node (ref "XP8") (pin "3") (pinfunction "3_3") (pintype "passive"))
    )
    (net (code "17") (name "Net-(D1-DOUT)") (class "Default")
      (node (ref "D1") (pin "2") (pinfunction "DOUT_2") (pintype "power_in"))
      (node (ref "D2") (pin "4") (pinfunction "DIN_4") (pintype "power_in"))
    )
    (net (code "18") (name "Net-(D2-DOUT)") (class "Default")
      (node (ref "D2") (pin "2") (pinfunction "DOUT_2") (pintype "power_in"))
      (node (ref "D3") (pin "4") (pinfunction "DIN_4") (pintype "power_in"))
    )
    (net (code "19") (name "Net-(D3-DOUT)") (class "Default")
      (node (ref "D3") (pin "2") (pinfunction "DOUT_2") (pintype "power_in"))
      (node (ref "D4") (pin "4") (pinfunction "DIN_4") (pintype "power_in"))
    )
    (net (code "20") (name "Net-(D4-DOUT)") (class "Default")
      (node (ref "D4") (pin "2") (pinfunction "DOUT_2") (pintype "power_in"))
      (node (ref "D5") (pin "4") (pinfunction "DIN_4") (pintype "power_in"))
    )
    (net (code "21") (name "Net-(D5-DOUT)") (class "Default")
      (node (ref "D5") (pin "2") (pinfunction "DOUT_2") (pintype "power_in"))
      (node (ref "D6") (pin "4") (pinfunction "DIN_4") (pintype "power_in"))
    )
    (net (code "22") (name "Net-(D6-DOUT)") (class "Default")
      (node (ref "D6") (pin "2") (pinfunction "DOUT_2") (pintype "power_in"))
      (node (ref "D7") (pin "4") (pinfunction "DIN_4") (pintype "power_in"))
    )
    (net (code "23") (name "Net-(D7-DOUT)") (class "Default")
      (node (ref "D7") (pin "2") (pinfunction "DOUT_2") (pintype "power_in"))
      (node (ref "D8") (pin "4") (pinfunction "DIN_4") (pintype "power_in"))
    )
    (net (code "24") (name "Net-(D8-DOUT)") (class "Default")
      (node (ref "D8") (pin "2") (pinfunction "DOUT_2") (pintype "power_in"))
      (node (ref "D9") (pin "4") (pinfunction "DIN_4") (pintype "power_in"))
    )
    (net (code "25") (name "Net-(D10-DIN)") (class "Default")
      (node (ref "D10") (pin "4") (pinfunction "DIN_4") (pintype "power_in"))
      (node (ref "D9") (pin "2") (pinfunction "DOUT_2") (pintype "power_in"))
    )
    (net (code "26") (name "Net-(D10-DOUT)") (class "Default")
      (node (ref "D10") (pin "2") (pinfunction "DOUT_2") (pintype "power_in"))
      (node (ref "D11") (pin "4") (pinfunction "DIN_4") (pintype "power_in"))
    )
    (net (code "27") (name "Net-(D11-DOUT)") (class "Default")
      (node (ref "D11") (pin "2") (pinfunction "DOUT_2") (pintype "power_in"))
      (node (ref "D12") (pin "4") (pinfunction "DIN_4") (pintype "power_in"))
    )
    (net (code "28") (name "Net-(D12-DOUT)") (class "Default")
      (node (ref "D12") (pin "2") (pinfunction "DOUT_2") (pintype "power_in"))
      (node (ref "D13") (pin "4") (pinfunction "DIN_4") (pintype "power_in"))
    )
    (net (code "29") (name "Net-(D13-DOUT)") (class "Default")
      (node (ref "D13") (pin "2") (pinfunction "DOUT_2") (pintype "power_in"))
      (node (ref "D14") (pin "4") (pinfunction "DIN_4") (pintype "power_in"))
    )
    (net (code "30") (name "Net-(D14-DOUT)") (class "Default")
      (node (ref "D14") (pin "2") (pinfunction "DOUT_2") (pintype "power_in"))
      (node (ref "D15") (pin "4") (pinfunction "DIN_4") (pintype "power_in"))
    )
    (net (code "31") (name "Net-(D15-DOUT)") (class "Default")
      (node (ref "D15") (pin "2") (pinfunction "DOUT_2") (pintype "power_in"))
      (node (ref "D16") (pin "4") (pinfunction "DIN_4") (pintype "power_in"))
    )
    (net (code "32") (name "Net-(D17-PadA)") (class "Default")
      (node (ref "D17") (pin "A") (pinfunction "A_A") (pintype "passive"))
      (node (ref "R10") (pin "2") (pinfunction "2_2") (pintype "passive"))
    )
    (net (code "33") (name "Net-(R5-Pad2)") (class "Default")
      (node (ref "R5") (pin "2") (pinfunction "2_2") (pintype "passive"))
      (node (ref "Y1") (pin "2") (pinfunction "2_2") (pintype "power_in"))
    )
    (net (code "34") (name "Net-(U1-OSC_IN{slash}PD0)") (class "Default")
      (node (ref "U1") (pin "2") (pinfunction "OSC_IN/PD0_2") (pintype "input"))
      (node (ref "Y1") (pin "1") (pinfunction "1_1") (pintype "passive"))
    )
    (net (code "35") (name "Net-(U1-OSC_OUT{slash}PD1)") (class "Default")
      (node (ref "U1") (pin "3") (pinfunction "OSC_OUT/PD1_3") (pintype "output"))
      (node (ref "Y1") (pin "3") (pinfunction "3_3") (pintype "passive"))
    )
    (net (code "36") (name "VCC") (class "Default")
      (node (ref "C1") (pin "1") (pinfunction "1_1") (pintype "passive"))
      (node (ref "C10") (pin "1") (pinfunction "1_1") (pintype "passive"))
      (node (ref "C11") (pin "1") (pinfunction "1_1") (pintype "passive"))
      (node (ref "C12") (pin "1") (pinfunction "1_1") (pintype "passive"))
      (node (ref "C13") (pin "1") (pinfunction "1_1") (pintype "passive"))
      (node (ref "C14") (pin "1") (pinfunction "1_1") (pintype "passive"))
      (node (ref "C15") (pin "1") (pinfunction "1_1") (pintype "passive"))
      (node (ref "C16") (pin "1") (pinfunction "1_1") (pintype "passive"))
      (node (ref "C17") (pin "2") (pinfunction "2_2") (pintype "passive"))
      (node (ref "C18") (pin "2") (pinfunction "2_2") (pintype "passive"))
      (node (ref "C2") (pin "1") (pinfunction "1_1") (pintype "passive"))
      (node (ref "C23") (pin "1") (pinfunction "1_1") (pintype "passive"))
      (node (ref "C25") (pin "1") (pinfunction "1_1") (pintype "passive"))
      (node (ref "C3") (pin "1") (pinfunction "1_1") (pintype "passive"))
      (node (ref "C4") (pin "1") (pinfunction "1_1") (pintype "passive"))
      (node (ref "C5") (pin "1") (pinfunction "1_1") (pintype "passive"))
      (node (ref "C6") (pin "1") (pinfunction "1_1") (pintype "passive"))
      (node (ref "C7") (pin "1") (pinfunction "1_1") (pintype "passive"))
      (node (ref "C8") (pin "1") (pinfunction "1_1") (pintype "passive"))
      (node (ref "C9") (pin "1") (pinfunction "1_1") (pintype "passive"))
      (node (ref "CAN-AP1") (pin "1") (pinfunction "1_1") (pintype "passive"))
      (node (ref "D1") (pin "1") (pinfunction "Vdd_1") (pintype "power_in"))
      (node (ref "D10") (pin "1") (pinfunction "Vdd_1") (pintype "power_in"))
      (node (ref "D11") (pin "1") (pinfunction "Vdd_1") (pintype "power_in"))
      (node (ref "D12") (pin "1") (pinfunction "Vdd_1") (pintype "power_in"))
      (node (ref "D13") (pin "1") (pinfunction "Vdd_1") (pintype "power_in"))
      (node (ref "D14") (pin "1") (pinfunction "Vdd_1") (pintype "power_in"))
      (node (ref "D15") (pin "1") (pinfunction "Vdd_1") (pintype "power_in"))
      (node (ref "D16") (pin "1") (pinfunction "Vdd_1") (pintype "power_in"))
      (node (ref "D2") (pin "1") (pinfunction "Vdd_1") (pintype "power_in"))
      (node (ref "D3") (pin "1") (pinfunction "Vdd_1") (pintype "power_in"))
      (node (ref "D4") (pin "1") (pinfunction "Vdd_1") (pintype "power_in"))
      (node (ref "D5") (pin "1") (pinfunction "Vdd_1") (pintype "power_in"))
      (node (ref "D6") (pin "1") (pinfunction "Vdd_1") (pintype "power_in"))
      (node (ref "D7") (pin "1") (pinfunction "Vdd_1") (pintype "power_in"))
      (node (ref "D8") (pin "1") (pinfunction "Vdd_1") (pintype "power_in"))
      (node (ref "D9") (pin "1") (pinfunction "Vdd_1") (pintype "power_in"))
      (node (ref "R3") (pin "2") (pinfunction "2_2") (pintype "passive"))
      (node (ref "R4") (pin "2") (pinfunction "2_2") (pintype "passive"))
      (node (ref "R8") (pin "2") (pinfunction "2_2") (pintype "passive"))
      (node (ref "U2") (pin "3") (pinfunction "VCC_3") (pintype "power_in"))
      (node (ref "U3") (pin "1") (pinfunction "VIN_1") (pintype "power_in"))
      (node (ref "U3") (pin "3") (pinfunction "EN_3") (pintype "input"))
      (node (ref "XP1") (pin "2") (pinfunction "2_2") (pintype "passive"))
      (node (ref "XP2") (pin "2") (pinfunction "2_2") (pintype "passive"))
      (node (ref "XP3") (pin "2") (pinfunction "2_2") (pintype "passive"))
      (node (ref "XP4") (pin "2") (pinfunction "2_2") (pintype "passive"))
      (node (ref "XP5") (pin "2") (pinfunction "2_2") (pintype "passive"))
      (node (ref "XP6") (pin "2") (pinfunction "2_2") (pintype "passive"))
      (node (ref "XP7") (pin "2") (pinfunction "2_2") (pintype "passive"))
      (node (ref "XP8") (pin "2") (pinfunction "2_2") (pintype "passive"))
    )
    (net (code "37") (name "unconnected-(SWD1-SHIELD-PadS1)") (class "Default")
      (node (ref "SWD1") (pin "S1") (pinfunction "SHIELD_S1") (pintype "passive"))
    )
    (net (code "38") (name "unconnected-(SWD1-SHIELD-PadS2)") (class "Default")
      (node (ref "SWD1") (pin "S2") (pinfunction "SHIELD_S2") (pintype "passive"))
    )
    (net (code "39") (name "unconnected-(U1-PA0-WKUP-Pad7)") (class "Default")
      (node (ref "U1") (pin "7") (pinfunction "PA0-WKUP_7") (pintype "bidirectional"))
    )
    (net (code "40") (name "unconnected-(U1-PA2-Pad9)") (class "Default")
      (node (ref "U1") (pin "9") (pinfunction "PA2_9") (pintype "bidirectional"))
    )
    (net (code "41") (name "unconnected-(U1-PA3-Pad10)") (class "Default")
      (node (ref "U1") (pin "10") (pinfunction "PA3_10") (pintype "bidirectional"))
    )
    (net (code "42") (name "unconnected-(U1-PA6-Pad13)") (class "Default")
      (node (ref "U1") (pin "13") (pinfunction "PA6_13") (pintype "bidirectional"))
    )
    (net (code "43") (name "unconnected-(U1-PA7-Pad14)") (class "Default")
      (node (ref "U1") (pin "14") (pinfunction "PA7_14") (pintype "bidirectional"))
    )
    (net (code "44") (name "unconnected-(U1-PA8-Pad20)") (class "Default")
      (node (ref "U1") (pin "20") (pinfunction "PA8_20") (pintype "bidirectional"))
    )
    (net (code "45") (name "unconnected-(U1-PA9-Pad21)") (class "Default")
      (node (ref "U1") (pin "21") (pinfunction "PA9_21") (pintype "bidirectional"))
    )
    (net (code "46") (name "unconnected-(U1-PA10-Pad22)") (class "Default")
      (node (ref "U1") (pin "22") (pinfunction "PA10_22") (pintype "bidirectional"))
    )
    (net (code "47") (name "unconnected-(U1-PB0-Pad15)") (class "Default")
      (node (ref "U1") (pin "15") (pinfunction "PB0_15") (pintype "bidirectional"))
    )
    (net (code "48") (name "unconnected-(U1-PB1-Pad16)") (class "Default")
      (node (ref "U1") (pin "16") (pinfunction "PB1_16") (pintype "bidirectional"))
    )
    (net (code "49") (name "unconnected-(U3-ADJ{slash}BYP-Pad4)") (class "Default")
      (node (ref "U3") (pin "4") (pinfunction "ADJ/BYP_4") (pintype "passive"))
    )
  )
)
